# source_eagle.net
KiCad netlist of a schematic drawn in EAGLE
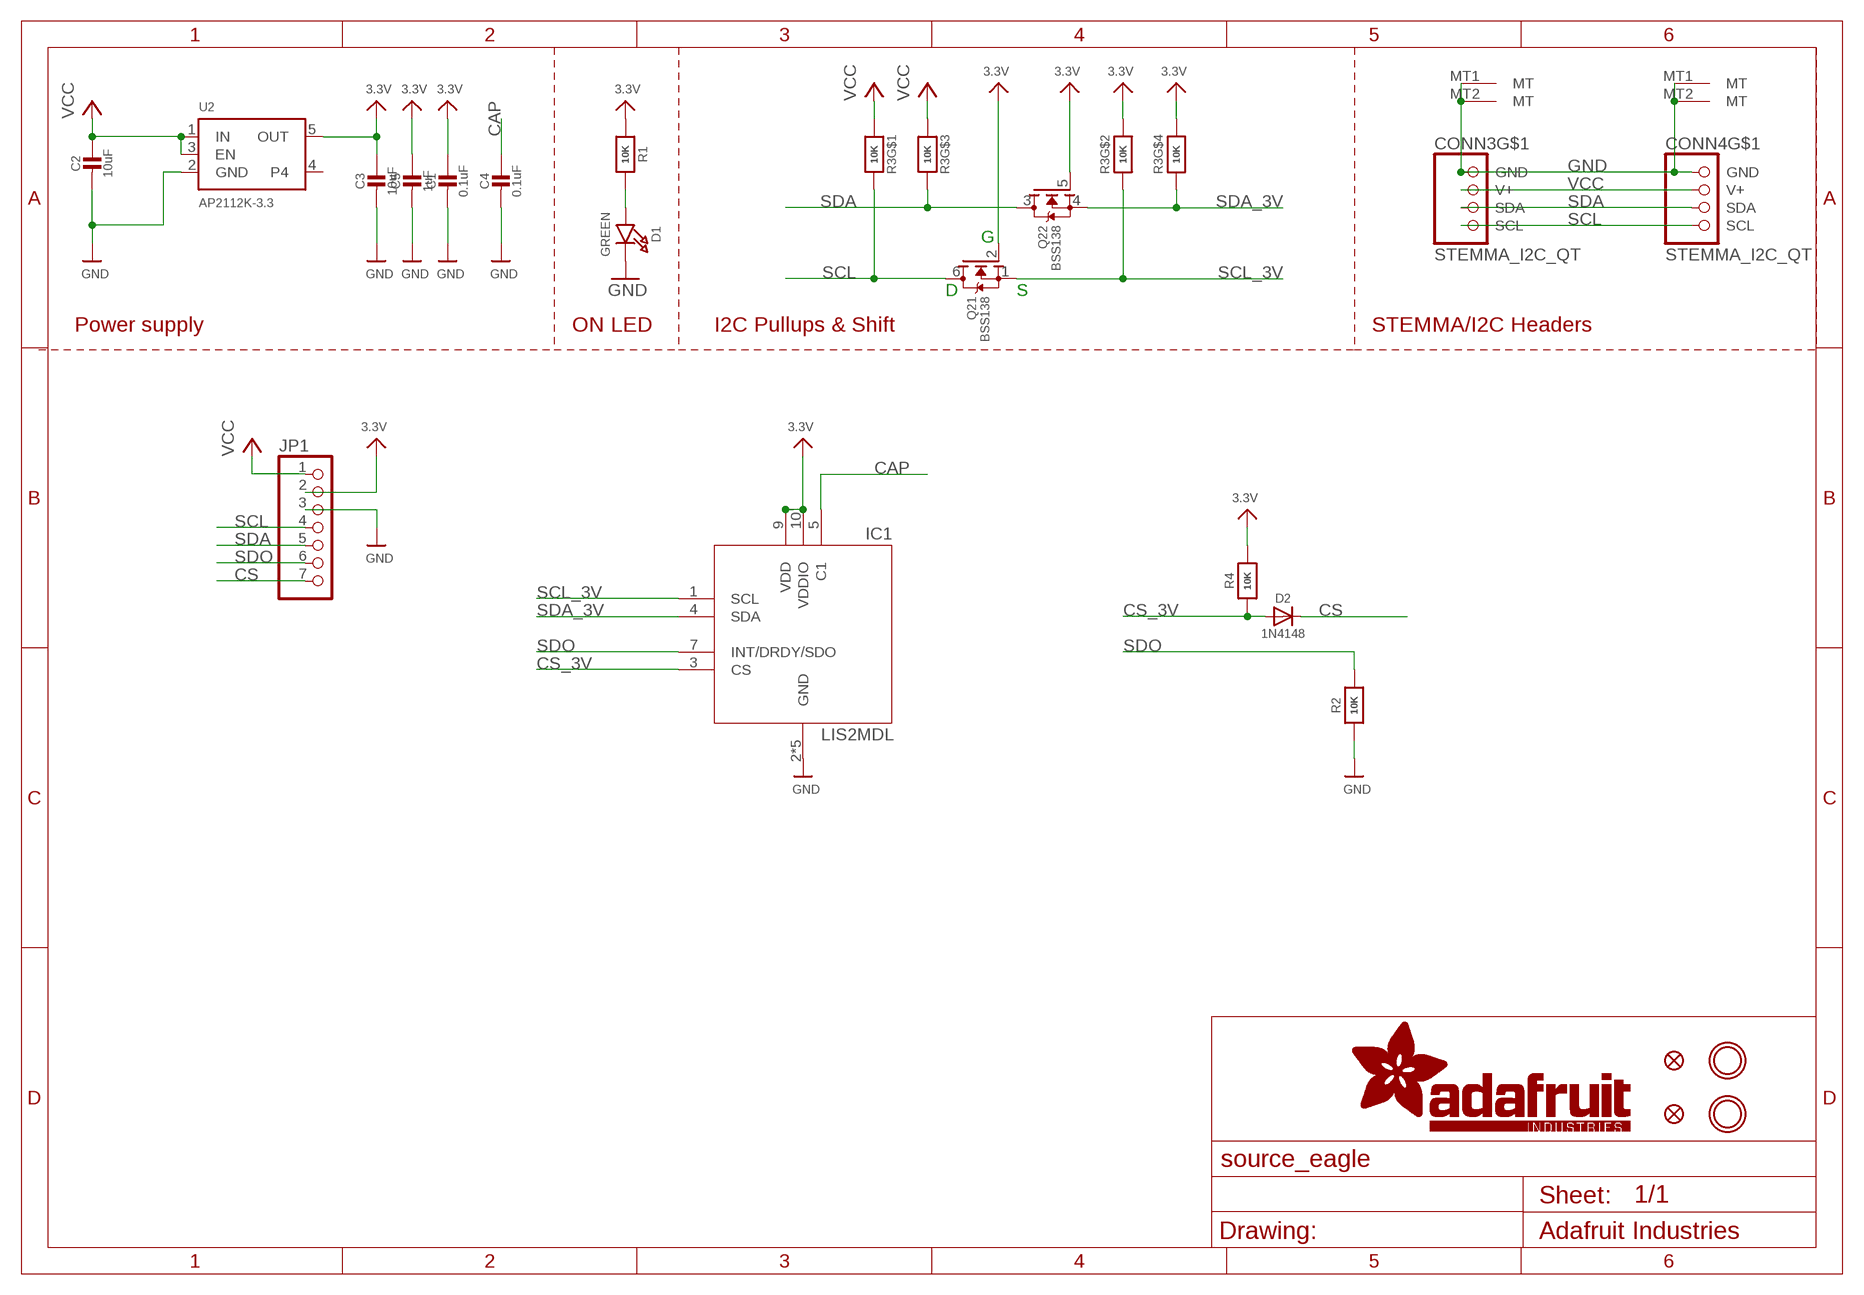
[diagram p0: schematic, sheet 1]

(export (version "E")
  (design (tool "Eeschema 10.0.6"))
  (components
    (comp (ref "C1")
      (value "0.1uF")
      (footprint "eagle-import:0603-NO")
      (libsource (lib "eagle-import") (part "CAP_CERAMIC0603_NO"))
    )
    (comp (ref "C2")
      (value "10uF")
      (footprint "eagle-import:0805-NO")
      (libsource (lib "eagle-import") (part "CAP_CERAMIC0805-NOOUTLINE"))
    )
    (comp (ref "C3")
      (value "10uF")
      (footprint "eagle-import:0805-NO")
      (libsource (lib "eagle-import") (part "CAP_CERAMIC0805-NOOUTLINE"))
    )
    (comp (ref "C4")
      (value "0.1uF")
      (footprint "eagle-import:0603-NO")
      (libsource (lib "eagle-import") (part "CAP_CERAMIC0603_NO"))
    )
    (comp (ref "C5")
      (value "1uF")
      (footprint "eagle-import:0603-NO")
      (libsource (lib "eagle-import") (part "CAP_CERAMIC0603_NO"))
    )
    (comp (ref "CONN3")
      (value "STEMMA_I2C_QT")
      (footprint "eagle-import:JST_SH4")
      (libsource (lib "eagle-import") (part "STEMMA_I2C_QT"))
    )
    (comp (ref "CONN4")
      (value "STEMMA_I2C_QT")
      (footprint "eagle-import:JST_SH4")
      (libsource (lib "eagle-import") (part "STEMMA_I2C_QT"))
    )
    (comp (ref "D1")
      (value "GREEN")
      (footprint "eagle-import:CHIPLED_0603_NOOUTLINE")
      (libsource (lib "eagle-import") (part "LED0603_NOOUTLINE"))
    )
    (comp (ref "D2")
      (value "1N4148")
      (footprint "eagle-import:SOD-323")
      (libsource (lib "eagle-import") (part "DIODESOD-323"))
    )
    (comp (ref "FID3")
      (value "FIDUCIAL_1MM")
      (footprint "eagle-import:FIDUCIAL_1MM")
      (libsource (lib "eagle-import") (part "FIDUCIAL_1MM"))
    )
    (comp (ref "FID4")
      (value "FIDUCIAL_1MM")
      (footprint "eagle-import:FIDUCIAL_1MM")
      (libsource (lib "eagle-import") (part "FIDUCIAL_1MM"))
    )
    (comp (ref "IC1")
      (value "LIS2MDL")
      (footprint "eagle-import:LGA12_2X2MM")
      (libsource (lib "eagle-import") (part "LIS2MDL"))
    )
    (comp (ref "JP1")
      (value "HEADER-1X770MIL")
      (footprint "eagle-import:1X07_ROUND_70")
      (libsource (lib "eagle-import") (part "HEADER-1X770MIL"))
    )
    (comp (ref "Q2")
      (value "BSS138")
      (footprint "eagle-import:SOT363")
      (libsource (lib "eagle-import") (part "MOSFET-N_DUAL"))
    )
    (comp (ref "R1")
      (value "10K")
      (footprint "eagle-import:0603-NO")
      (libsource (lib "eagle-import") (part "RESISTOR_0603_NOOUT"))
    )
    (comp (ref "R2")
      (value "10K")
      (footprint "eagle-import:0603-NO")
      (libsource (lib "eagle-import") (part "RESISTOR_0603_NOOUT"))
    )
    (comp (ref "R3")
      (value "10K")
      (footprint "eagle-import:RESPACK_4X0603")
      (libsource (lib "eagle-import") (part "RESISTOR_4PACK"))
    )
    (comp (ref "R4")
      (value "10K")
      (footprint "eagle-import:0603-NO")
      (libsource (lib "eagle-import") (part "RESISTOR_0603_NOOUT"))
    )
    (comp (ref "U$1")
      (value "MOUNTINGHOLE2.5")
      (footprint "eagle-import:MOUNTINGHOLE_2.5_PLATED")
      (libsource (lib "eagle-import") (part "MOUNTINGHOLE2.5"))
    )
    (comp (ref "U$17")
      (value "MOUNTINGHOLE2.5")
      (footprint "eagle-import:MOUNTINGHOLE_2.5_PLATED")
      (libsource (lib "eagle-import") (part "MOUNTINGHOLE2.5"))
    )
    (comp (ref "U2")
      (value "AP2112K-3.3")
      (footprint "eagle-import:SOT23-5")
      (libsource (lib "eagle-import") (part "VREG_SOT23-5"))
    )
  )
  (nets
    (net (code "1") (name "/CAP") (class "Default")
      (node (ref "C4") (pin "1") (pinfunction "1_1") (pintype "passive"))
      (node (ref "IC1") (pin "5") (pinfunction "C1_5") (pintype "input"))
    )
    (net (code "2") (name "/CS") (class "Default")
      (node (ref "D2") (pin "C") (pinfunction "C_C") (pintype "passive"))
      (node (ref "JP1") (pin "7") (pinfunction "7_7") (pintype "passive"))
    )
    (net (code "3") (name "/CS_3V") (class "Default")
      (node (ref "D2") (pin "A") (pinfunction "A_A") (pintype "passive"))
      (node (ref "IC1") (pin "3") (pinfunction "CS_3") (pintype "input"))
      (node (ref "R4") (pin "1") (pinfunction "1_1") (pintype "passive"))
    )
    (net (code "4") (name "/SCL") (class "Default")
      (node (ref "CONN3") (pin "4") (pinfunction "SCL_4") (pintype "passive"))
      (node (ref "CONN4") (pin "4") (pinfunction "SCL_4") (pintype "passive"))
      (node (ref "JP1") (pin "4") (pinfunction "4_4") (pintype "passive"))
      (node (ref "Q2") (pin "6") (pinfunction "D_6") (pintype "bidirectional"))
      (node (ref "R3") (pin "8") (pinfunction "2_8") (pintype "passive"))
    )
    (net (code "5") (name "/SCL_3V") (class "Default")
      (node (ref "IC1") (pin "1") (pinfunction "SCL_1") (pintype "input"))
      (node (ref "Q2") (pin "1") (pinfunction "S_1") (pintype "bidirectional"))
      (node (ref "R3") (pin "7") (pinfunction "2_7") (pintype "passive"))
    )
    (net (code "6") (name "/SDA") (class "Default")
      (node (ref "CONN3") (pin "3") (pinfunction "SDA_3") (pintype "passive"))
      (node (ref "CONN4") (pin "3") (pinfunction "SDA_3") (pintype "passive"))
      (node (ref "JP1") (pin "5") (pinfunction "5_5") (pintype "passive"))
      (node (ref "Q2") (pin "3") (pinfunction "D_3") (pintype "bidirectional"))
      (node (ref "R3") (pin "6") (pinfunction "2_6") (pintype "passive"))
    )
    (net (code "7") (name "/SDA_3V") (class "Default")
      (node (ref "IC1") (pin "4") (pinfunction "SDA_4") (pintype "bidirectional"))
      (node (ref "Q2") (pin "4") (pinfunction "S_4") (pintype "bidirectional"))
      (node (ref "R3") (pin "5") (pinfunction "2_5") (pintype "passive"))
    )
    (net (code "8") (name "/SDO") (class "Default")
      (node (ref "IC1") (pin "7") (pinfunction "INT/DRDY/SDO_7") (pintype "bidirectional"))
      (node (ref "JP1") (pin "6") (pinfunction "6_6") (pintype "passive"))
      (node (ref "R2") (pin "2") (pinfunction "2_2") (pintype "passive"))
    )
    (net (code "9") (name "3.3V") (class "Default")
      (node (ref "C1") (pin "1") (pinfunction "1_1") (pintype "passive"))
      (node (ref "C3") (pin "1") (pinfunction "1_1") (pintype "passive"))
      (node (ref "C5") (pin "1") (pinfunction "1_1") (pintype "passive"))
      (node (ref "IC1") (pin "10") (pinfunction "VDDIO_10") (pintype "power_in"))
      (node (ref "IC1") (pin "9") (pinfunction "VDD_9") (pintype "power_in"))
      (node (ref "JP1") (pin "2") (pinfunction "2_2") (pintype "passive"))
      (node (ref "Q2") (pin "2") (pinfunction "G_2") (pintype "bidirectional"))
      (node (ref "Q2") (pin "5") (pinfunction "G_5") (pintype "bidirectional"))
      (node (ref "R1") (pin "1") (pinfunction "1_1") (pintype "passive"))
      (node (ref "R3") (pin "2") (pinfunction "1_2") (pintype "passive"))
      (node (ref "R3") (pin "4") (pinfunction "1_4") (pintype "passive"))
      (node (ref "R4") (pin "2") (pinfunction "2_2") (pintype "passive"))
      (node (ref "U2") (pin "5") (pinfunction "OUT_5") (pintype "power_in"))
    )
    (net (code "10") (name "GND") (class "Default")
      (node (ref "C1") (pin "2") (pinfunction "2_2") (pintype "passive"))
      (node (ref "C2") (pin "2") (pinfunction "2_2") (pintype "passive"))
      (node (ref "C3") (pin "2") (pinfunction "2_2") (pintype "passive"))
      (node (ref "C4") (pin "2") (pinfunction "2_2") (pintype "passive"))
      (node (ref "C5") (pin "2") (pinfunction "2_2") (pintype "passive"))
      (node (ref "CONN3") (pin "1") (pinfunction "GND_1") (pintype "passive"))
      (node (ref "CONN3") (pin "MT1") (pinfunction "MT_MT1") (pintype "bidirectional"))
      (node (ref "CONN3") (pin "MT2") (pinfunction "MT_MT2") (pintype "bidirectional"))
      (node (ref "CONN4") (pin "1") (pinfunction "GND_1") (pintype "passive"))
      (node (ref "CONN4") (pin "MT1") (pinfunction "MT_MT1") (pintype "bidirectional"))
      (node (ref "CONN4") (pin "MT2") (pinfunction "MT_MT2") (pintype "bidirectional"))
      (node (ref "D1") (pin "C") (pinfunction "C_C") (pintype "passive"))
      (node (ref "IC1") (pin "11") (pinfunction "GND_11") (pintype "power_in"))
      (node (ref "IC1") (pin "12") (pinfunction "GND_12") (pintype "power_in"))
      (node (ref "IC1") (pin "2") (pinfunction "GND_2") (pintype "power_in"))
      (node (ref "IC1") (pin "6") (pinfunction "GND_6") (pintype "power_in"))
      (node (ref "IC1") (pin "8") (pinfunction "GND_8") (pintype "power_in"))
      (node (ref "JP1") (pin "3") (pinfunction "3_3") (pintype "passive"))
      (node (ref "R2") (pin "1") (pinfunction "1_1") (pintype "passive"))
      (node (ref "U2") (pin "2") (pinfunction "GND_2") (pintype "power_in"))
    )
    (net (code "11") (name "Net-(D1-PadA)") (class "Default")
      (node (ref "D1") (pin "A") (pinfunction "A_A") (pintype "passive"))
      (node (ref "R1") (pin "2") (pinfunction "2_2") (pintype "passive"))
    )
    (net (code "12") (name "VCC") (class "Default")
      (node (ref "C2") (pin "1") (pinfunction "1_1") (pintype "passive"))
      (node (ref "CONN3") (pin "2") (pinfunction "V+_2") (pintype "passive"))
      (node (ref "CONN4") (pin "2") (pinfunction "V+_2") (pintype "passive"))
      (node (ref "JP1") (pin "1") (pinfunction "1_1") (pintype "passive"))
      (node (ref "R3") (pin "1") (pinfunction "1_1") (pintype "passive"))
      (node (ref "R3") (pin "3") (pinfunction "1_3") (pintype "passive"))
      (node (ref "U2") (pin "1") (pinfunction "IN_1") (pintype "power_in"))
      (node (ref "U2") (pin "3") (pinfunction "EN_3") (pintype "input"))
    )
    (net (code "13") (name "unconnected-(U2-P4-Pad4)") (class "Default")
      (node (ref "U2") (pin "4") (pinfunction "P4_4") (pintype "bidirectional"))
    )
  )
)
